# CR2.net
KiCad netlist of a schematic drawn in EasyEDA Pro
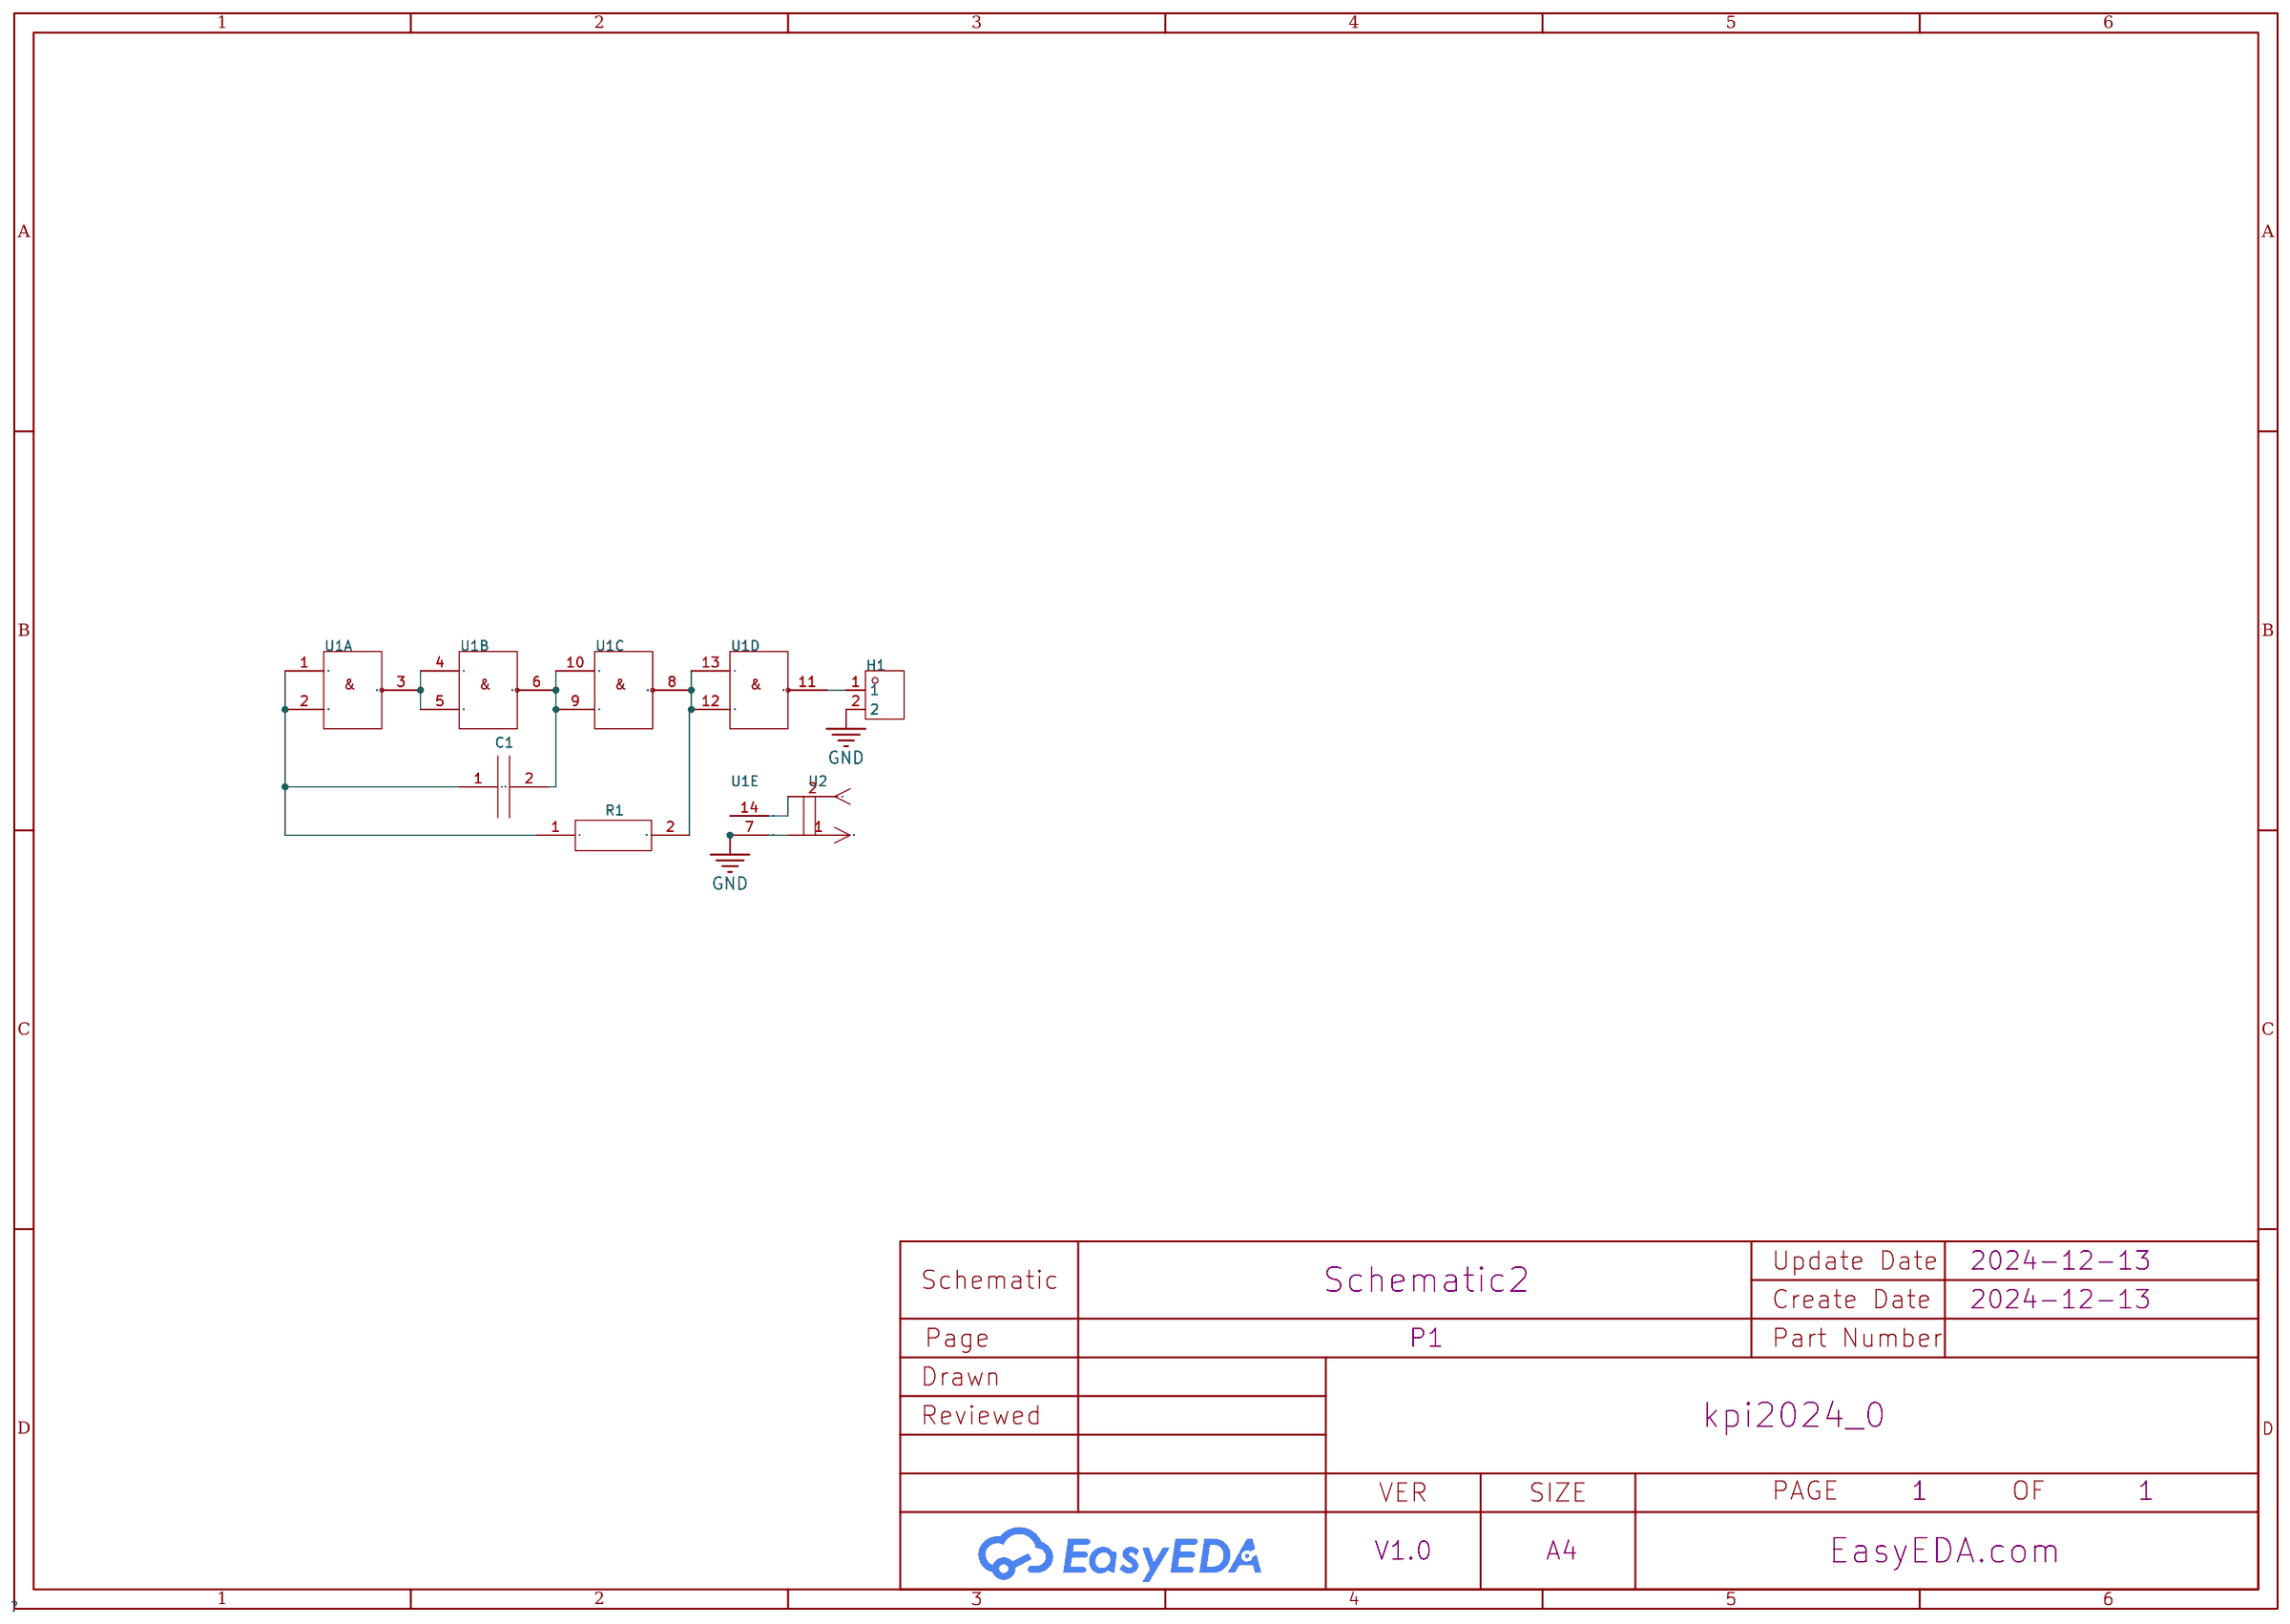
[diagram p0: schematic sheet]

(export (version "E")
  (design (tool "Eeschema 10.0.6"))
  (components
    (comp (ref "C1") (value "~") (libsource (lib "easyedapro") (part "Cap К10-17Б")))
    (comp (ref "H1")
      (value "DZ200R-11-14-39")
      (footprint "easyedapro:HDR-TH_14P-P2.00-V-M")
      (fields (field (name "Manufacturer") "DEALON(德艺隆)"))
      (libsource (lib "easyedapro") (part "PLS-2"))
    )
    (comp (ref "U1")
      (value "~")
      (footprint "easyedapro:PDIP-14_L19.2-W6.6-P2.54-LS7.6-BL")
      (libsource (lib "easyedapro") (part "SN7400(NAND)"))
    )
    (comp (ref "U2")
      (value "~")
      (footprint "easyedapro:DS-210")
      (libsource (lib "easyedapro") (part "DS-210"))
    )
    (comp (ref "U3")
      (value "R1")
      (footprint "easyedapro:RES_CONST_L6.0D0.8")
      (libsource (lib "easyedapro") (part "Res MF 0.25"))
    )
  )
  (nets
    (net (code "1") (name "GND") (class "Default")
      (node (ref "H1") (pin "2") (pinfunction "2_2") (pintype "unspecified"))
      (node (ref "U1") (pin "7") (pinfunction "5_7") (pintype "input"))
      (node (ref "U2") (pin "1") (pinfunction "1_1") (pintype "input"))
    )
    (net (code "2") (name "Net-(C1-Pad1)") (class "Default")
      (node (ref "C1") (pin "1") (pinfunction "1_1") (pintype "input"))
      (node (ref "U1") (pin "1") (pinfunction "1_1") (pintype "input"))
      (node (ref "U1") (pin "2") (pinfunction "2_2") (pintype "input"))
      (node (ref "U3") (pin "1") (pinfunction "1_1") (pintype "input"))
    )
    (net (code "3") (name "Net-(U1B-1)") (class "Default")
      (node (ref "U1") (pin "3") (pinfunction "3_3") (pintype "input"))
      (node (ref "U1") (pin "4") (pinfunction "1_4") (pintype "input"))
      (node (ref "U1") (pin "5") (pinfunction "2_5") (pintype "input"))
    )
    (net (code "4") (name "Net-(U1B-3)") (class "Default")
      (node (ref "C1") (pin "2") (pinfunction "2_2") (pintype "input"))
      (node (ref "U1") (pin "10") (pinfunction "1_10") (pintype "input"))
      (node (ref "U1") (pin "6") (pinfunction "3_6") (pintype "input"))
      (node (ref "U1") (pin "9") (pinfunction "2_9") (pintype "input"))
    )
    (net (code "5") (name "Net-(U1C-3)") (class "Default")
      (node (ref "U1") (pin "12") (pinfunction "2_12") (pintype "input"))
      (node (ref "U1") (pin "13") (pinfunction "1_13") (pintype "input"))
      (node (ref "U1") (pin "8") (pinfunction "3_8") (pintype "input"))
      (node (ref "U3") (pin "2") (pinfunction "2_2") (pintype "input"))
    )
    (net (code "6") (name "Net-(U1D-3)") (class "Default")
      (node (ref "H1") (pin "1") (pinfunction "1_1") (pintype "unspecified"))
      (node (ref "U1") (pin "11") (pinfunction "3_11") (pintype "input"))
    )
    (net (code "7") (name "Net-(U1E-4)") (class "Default")
      (node (ref "U1") (pin "14") (pinfunction "4_14") (pintype "input"))
      (node (ref "U2") (pin "2") (pinfunction "2_2") (pintype "input"))
    )
  )
)
